# Shield_V4_Connector.net
KiCad netlist of a schematic drawn in EasyEDA
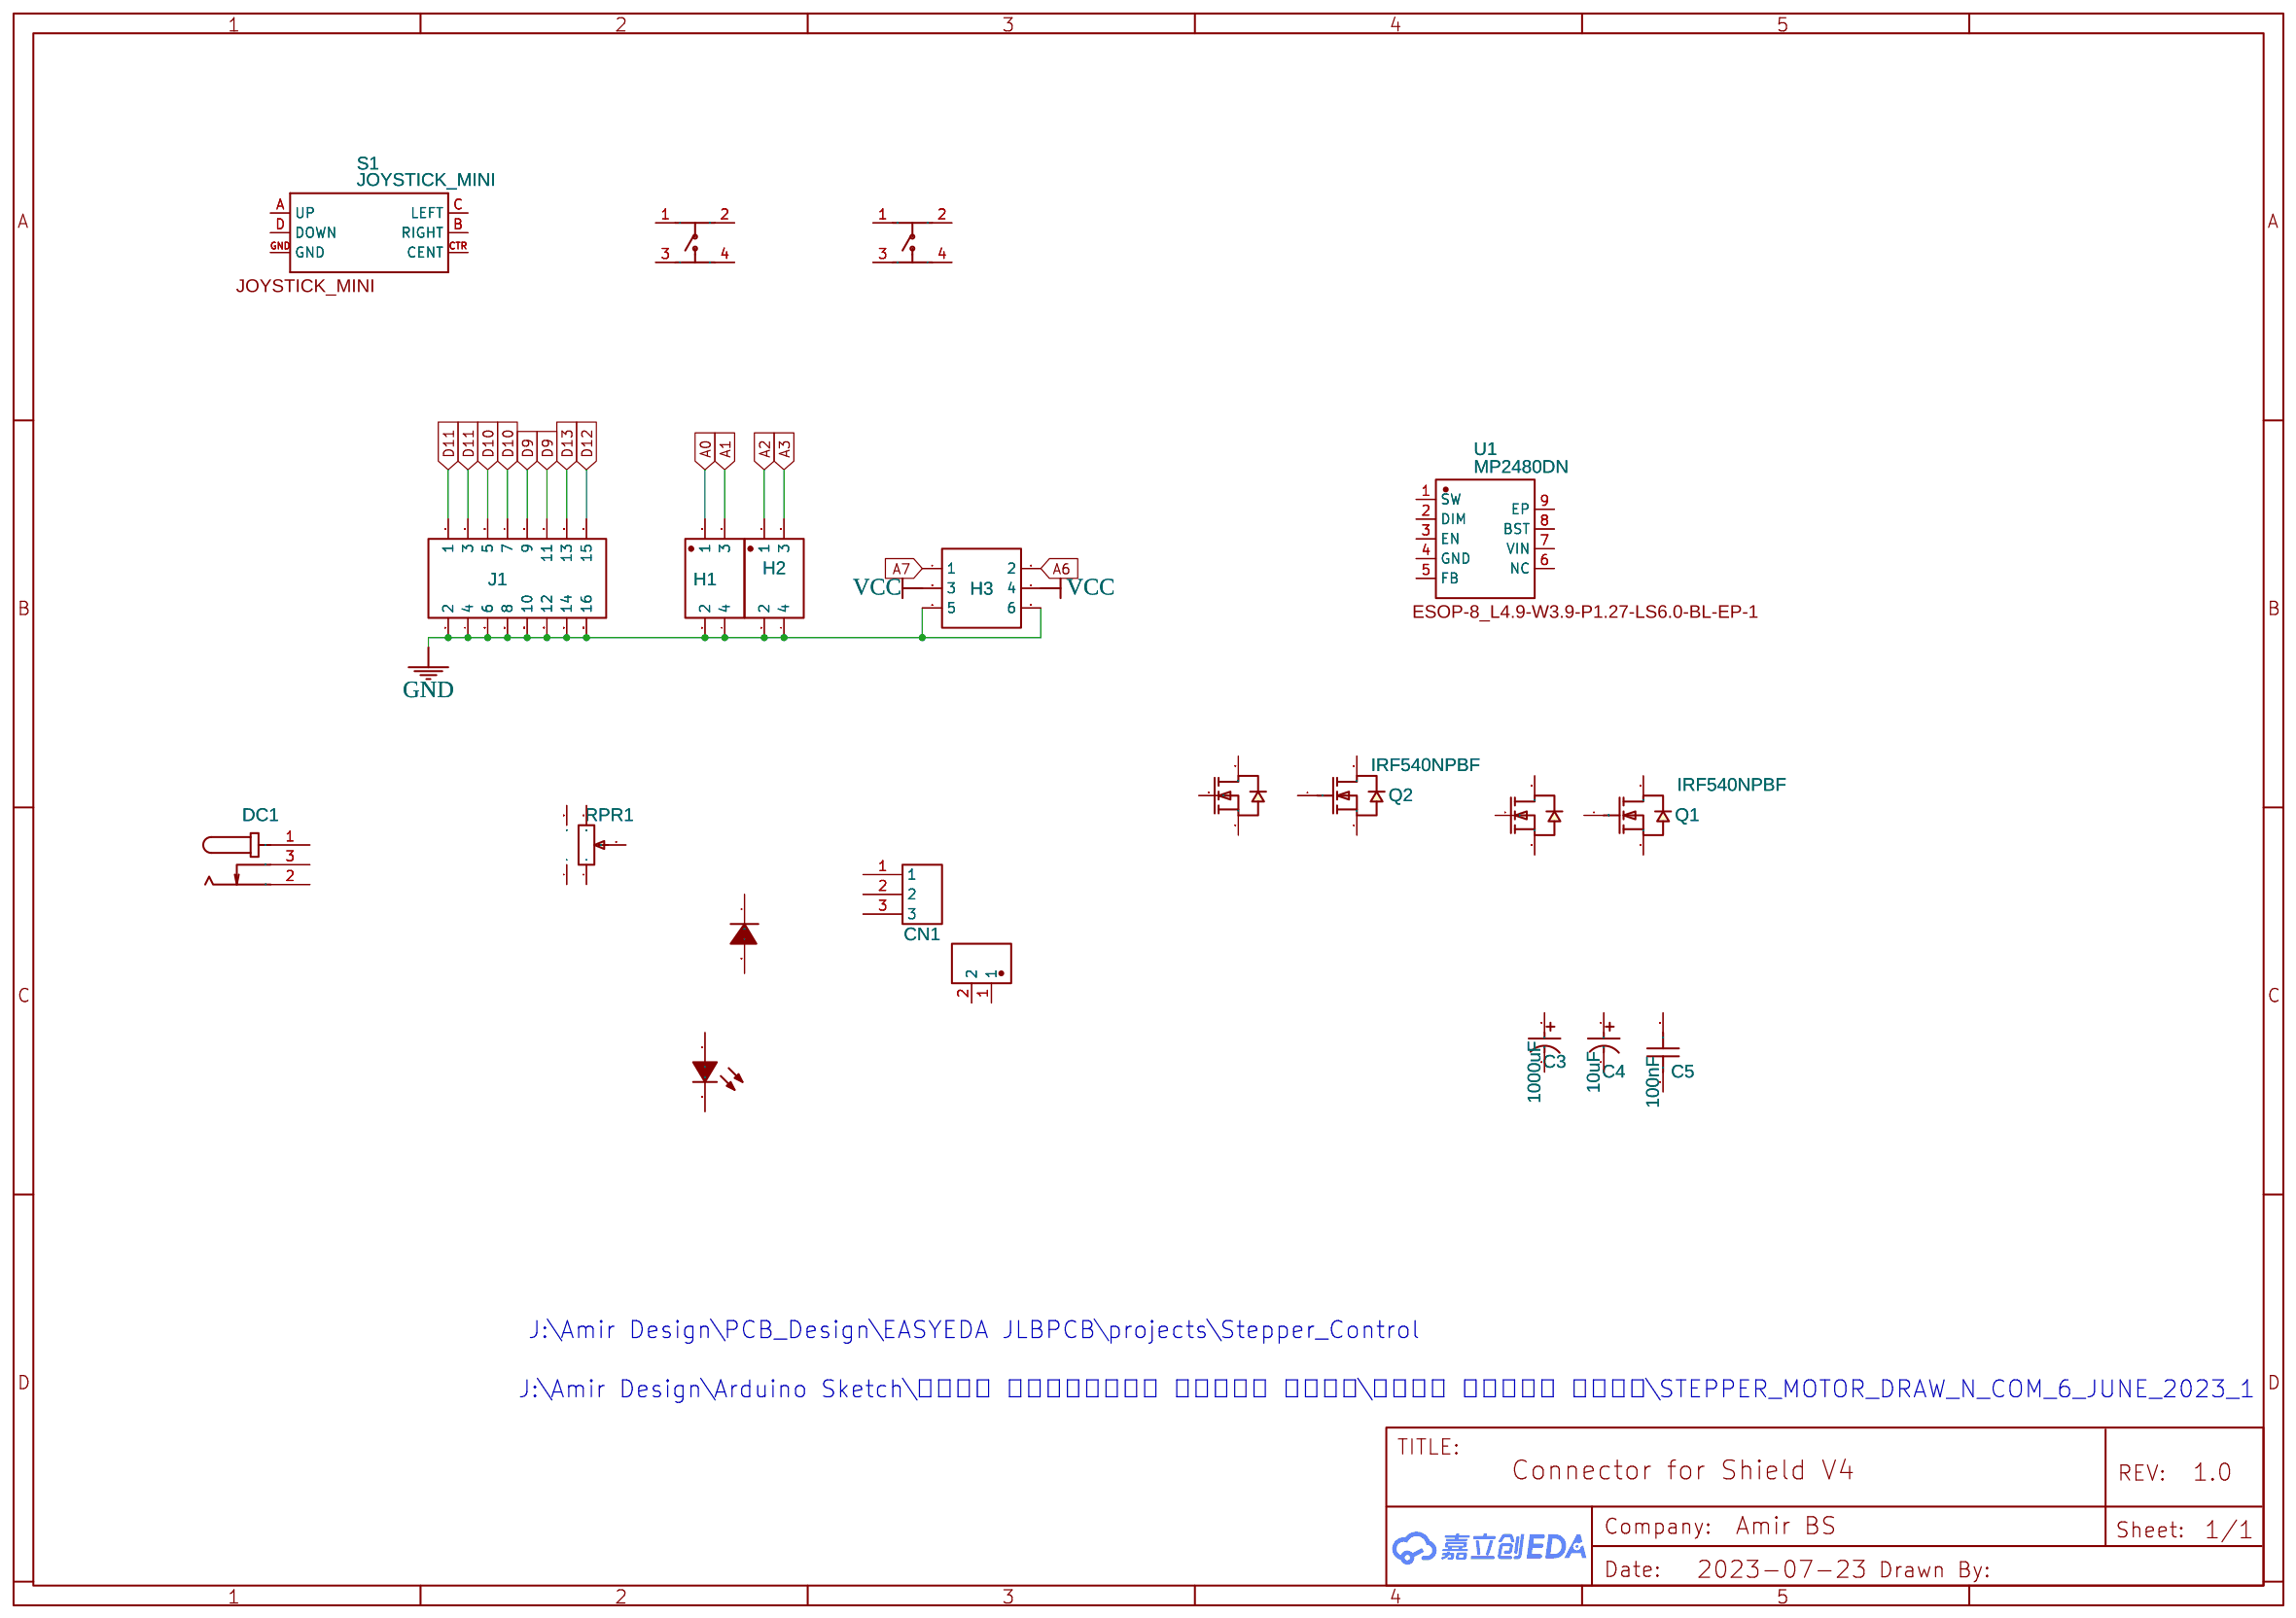
[diagram p0: schematic sheet]

(export (version "E")
  (design (tool "Eeschema 10.0.6"))
  (components
    (comp (ref "ACON1")
      (value "CON")
      (fields (field (name "BOM_Manufacturer Part") "PH-2AW") (field (name "BOM_Supplier Part") "C722769"))
      (libsource (lib "") (part "PH-2AW"))
    )
    (comp (ref "C3")
      (value "1000uF")
      (fields
        (field (name "BOM_Manufacturer Part") "KF102M025G200A")
        (field (name "BOM_Supplier Part") "C59326")
      )
      (libsource (lib "") (part "KF102M025G200A"))
    )
    (comp (ref "C4")
      (value "10uF")
      (fields
        (field (name "BOM_Manufacturer Part") "KF106M025C05RR0VH2FP0")
        (field (name "BOM_Supplier Part") "C43846")
      )
      (libsource (lib "") (part "10uF 25V 4*5"))
    )
    (comp (ref "C5")
      (value "100nF")
      (fields
        (field (name "BOM_Manufacturer Part") "CC0603KRX7R9BB104")
        (field (name "BOM_Supplier Part") "C14663")
      )
      (libsource (lib "") (part "CC0603KRX7R9BB104"))
    )
    (comp (ref "CN1")
      (value "XHB-3A")
      (fields (field (name "BOM_Supplier Part") "C68817"))
      (libsource (lib "") (part "XHB-3A"))
    )
    (comp (ref "DC1")
      (value "DC")
      (fields
        (field (name "BOM_Manufacturer Part") "DC005-2.0MM")
        (field (name "BOM_Supplier Part") "C111567")
      )
      (libsource (lib "") (part "DC005-2.0MM"))
    )
    (comp (ref "H1")
      (value "Header-Female-2.54_2x2")
      (fields
        (field (name "BOM_Manufacturer Part") "DS1023-2*2SF11")
        (field (name "BOM_Supplier Part") "C92273")
      )
      (libsource (lib "") (part "Header-Female-2.54_2x2"))
    )
    (comp (ref "H2")
      (value "Header-Female-2.54_2x2")
      (fields
        (field (name "BOM_Manufacturer Part") "DS1023-2*2SF11")
        (field (name "BOM_Supplier Part") "C92273")
      )
      (libsource (lib "") (part "Header-Female-2.54_2x2"))
    )
    (comp (ref "H3")
      (value "Header-Female-2.54_2x3")
      (fields
        (field (name "BOM_Manufacturer Part") "DS1023-2*3SF11")
        (field (name "BOM_Supplier Part") "C92272")
      )
      (libsource (lib "") (part "Header-Female-2.54_2x3"))
    )
    (comp (ref "HQ1")
      (value "Q")
      (fields (field (name "BOM_Manufacturer Part") "JSM2302") (field (name "BOM_Supplier Part") "C916403"))
      (libsource (lib "") (part "JSM2302"))
    )
    (comp (ref "HQ2")
      (value "Q")
      (fields (field (name "BOM_Manufacturer Part") "JSM2302") (field (name "BOM_Supplier Part") "C916403"))
      (libsource (lib "") (part "JSM2302"))
    )
    (comp (ref "ID1")
      (value "D")
      (fields (field (name "BOM_Manufacturer Part") "1N4007F") (field (name "BOM_Supplier Part") "C110856"))
      (libsource (lib "") (part "1N4007F"))
    )
    (comp (ref "ILED1")
      (value "LED")
      (fields
        (field (name "BOM_Manufacturer Part") "19-217/BHC-ZL1M2RY/3T")
        (field (name "BOM_Supplier Part") "C72041")
      )
      (libsource (lib "") (part "19-217/BHC-ZL1M2RY/3T"))
    )
    (comp (ref "J1")
      (value "Header-Female-2.54_2x8")
      (fields (field (name "BOM_Manufacturer Part") "2.54-2*8P母") (field (name "BOM_Supplier Part") "C30734"))
      (libsource (lib "") (part "Header-Female-2.54_2x8"))
    )
    (comp (ref "KEY1")
      (value "B3F-4050")
      (fields (field (name "BOM_Supplier Part") "C86707"))
      (libsource (lib "") (part "B3F-4050"))
    )
    (comp (ref "KEY2")
      (value "B3F-4050")
      (fields (field (name "BOM_Supplier Part") "C86707"))
      (libsource (lib "") (part "B3F-4050"))
    )
    (comp (ref "Q1")
      (value "IRF540NPBF")
      (fields (field (name "Manufacturer") "Infineon(英飞凌)"))
      (libsource (lib "") (part "IRF540NPBF"))
    )
    (comp (ref "Q2")
      (value "IRF540NPBF")
      (fields (field (name "Manufacturer") "Infineon(英飞凌)"))
      (libsource (lib "") (part "IRF540NPBF"))
    )
    (comp (ref "RPR1")
      (value "长柄旋转电位器")
      (fields (field (name "BOM_Supplier Part") "C2874842"))
      (libsource (lib "") (part "长柄旋转电位器"))
    )
    (comp (ref "S1") (value "JOYSTICK_MINI") (libsource (lib "") (part "JOYSTICK_MINI")))
    (comp (ref "U1") (value "MP2480DN") (libsource (lib "") (part "MP2480DN")))
  )
  (nets
    (net (code "1") (name "A0") (class "Default")
      (node (ref "H1") (pin "1") (pinfunction "1_1") (pintype "unspecified"))
    )
    (net (code "2") (name "A1") (class "Default")
      (node (ref "H1") (pin "3") (pinfunction "3_3") (pintype "unspecified"))
    )
    (net (code "3") (name "A2") (class "Default")
      (node (ref "H2") (pin "1") (pinfunction "1_1") (pintype "unspecified"))
    )
    (net (code "4") (name "A3") (class "Default")
      (node (ref "H2") (pin "3") (pinfunction "3_3") (pintype "unspecified"))
    )
    (net (code "5") (name "A6") (class "Default")
      (node (ref "H3") (pin "2") (pinfunction "2_2") (pintype "input"))
    )
    (net (code "6") (name "A7") (class "Default")
      (node (ref "H3") (pin "1") (pinfunction "1_1") (pintype "input"))
    )
    (net (code "7") (name "D9") (class "Default")
      (node (ref "J1") (pin "11") (pinfunction "11_11") (pintype "input"))
      (node (ref "J1") (pin "9") (pinfunction "9_9") (pintype "input"))
    )
    (net (code "8") (name "D10") (class "Default")
      (node (ref "J1") (pin "5") (pinfunction "5_5") (pintype "input"))
      (node (ref "J1") (pin "7") (pinfunction "7_7") (pintype "input"))
    )
    (net (code "9") (name "D11") (class "Default")
      (node (ref "J1") (pin "1") (pinfunction "1_1") (pintype "input"))
      (node (ref "J1") (pin "3") (pinfunction "3_3") (pintype "input"))
    )
    (net (code "10") (name "D12") (class "Default")
      (node (ref "J1") (pin "15") (pinfunction "15_15") (pintype "input"))
    )
    (net (code "11") (name "D13") (class "Default")
      (node (ref "J1") (pin "13") (pinfunction "13_13") (pintype "input"))
    )
    (net (code "12") (name "GND") (class "Default")
      (node (ref "H1") (pin "2") (pinfunction "2_2") (pintype "unspecified"))
      (node (ref "H1") (pin "4") (pinfunction "4_4") (pintype "unspecified"))
      (node (ref "H2") (pin "2") (pinfunction "2_2") (pintype "unspecified"))
      (node (ref "H2") (pin "4") (pinfunction "4_4") (pintype "unspecified"))
      (node (ref "H3") (pin "5") (pinfunction "5_5") (pintype "input"))
      (node (ref "H3") (pin "6") (pinfunction "6_6") (pintype "input"))
      (node (ref "J1") (pin "10") (pinfunction "10_10") (pintype "input"))
      (node (ref "J1") (pin "12") (pinfunction "12_12") (pintype "input"))
      (node (ref "J1") (pin "14") (pinfunction "14_14") (pintype "input"))
      (node (ref "J1") (pin "16") (pinfunction "16_16") (pintype "input"))
      (node (ref "J1") (pin "2") (pinfunction "2_2") (pintype "input"))
      (node (ref "J1") (pin "4") (pinfunction "4_4") (pintype "input"))
      (node (ref "J1") (pin "6") (pinfunction "6_6") (pintype "input"))
      (node (ref "J1") (pin "8") (pinfunction "8_8") (pintype "input"))
    )
    (net (code "13") (name "VCC") (class "Default")
      (node (ref "H3") (pin "3") (pinfunction "3_3") (pintype "input"))
      (node (ref "H3") (pin "4") (pinfunction "4_4") (pintype "input"))
    )
    (net (code "14") (name "unconnected-(ACON1-Pad1)") (class "Default")
      (node (ref "ACON1") (pin "1") (pinfunction "1_1") (pintype "unspecified"))
    )
    (net (code "15") (name "unconnected-(ACON1-Pad2)") (class "Default")
      (node (ref "ACON1") (pin "2") (pinfunction "2_2") (pintype "unspecified"))
    )
    (net (code "16") (name "unconnected-(C3-Pad1)") (class "Default")
      (node (ref "C3") (pin "1") (pinfunction "1_1") (pintype "input"))
    )
    (net (code "17") (name "unconnected-(C3-Pad2)") (class "Default")
      (node (ref "C3") (pin "2") (pinfunction "2_2") (pintype "input"))
    )
    (net (code "18") (name "unconnected-(C4-Pad1)") (class "Default")
      (node (ref "C4") (pin "1") (pinfunction "1_1") (pintype "input"))
    )
    (net (code "19") (name "unconnected-(C4-Pad2)") (class "Default")
      (node (ref "C4") (pin "2") (pinfunction "2_2") (pintype "input"))
    )
    (net (code "20") (name "unconnected-(C5-Pad1)") (class "Default")
      (node (ref "C5") (pin "1") (pinfunction "1_1") (pintype "unspecified"))
    )
    (net (code "21") (name "unconnected-(C5-Pad2)") (class "Default")
      (node (ref "C5") (pin "2") (pinfunction "2_2") (pintype "unspecified"))
    )
    (net (code "22") (name "unconnected-(CN1-Pad1)") (class "Default")
      (node (ref "CN1") (pin "1") (pinfunction "1_1") (pintype "unspecified"))
    )
    (net (code "23") (name "unconnected-(CN1-Pad2)") (class "Default")
      (node (ref "CN1") (pin "2") (pinfunction "2_2") (pintype "unspecified"))
    )
    (net (code "24") (name "unconnected-(CN1-Pad3)") (class "Default")
      (node (ref "CN1") (pin "3") (pinfunction "3_3") (pintype "unspecified"))
    )
    (net (code "25") (name "unconnected-(DC1-Pad1)") (class "Default")
      (node (ref "DC1") (pin "1") (pinfunction "1_1") (pintype "unspecified"))
    )
    (net (code "26") (name "unconnected-(DC1-Pad2)") (class "Default")
      (node (ref "DC1") (pin "2") (pinfunction "2_2") (pintype "unspecified"))
    )
    (net (code "27") (name "unconnected-(DC1-Pad3)") (class "Default")
      (node (ref "DC1") (pin "3") (pinfunction "3_3") (pintype "unspecified"))
    )
    (net (code "28") (name "unconnected-(HQ1-D-Pad3)") (class "Default")
      (node (ref "HQ1") (pin "3") (pinfunction "D_3") (pintype "unspecified"))
    )
    (net (code "29") (name "unconnected-(HQ1-G-Pad1)") (class "Default")
      (node (ref "HQ1") (pin "1") (pinfunction "G_1") (pintype "unspecified"))
    )
    (net (code "30") (name "unconnected-(HQ1-S-Pad2)") (class "Default")
      (node (ref "HQ1") (pin "2") (pinfunction "S_2") (pintype "unspecified"))
    )
    (net (code "31") (name "unconnected-(HQ2-D-Pad3)") (class "Default")
      (node (ref "HQ2") (pin "3") (pinfunction "D_3") (pintype "unspecified"))
    )
    (net (code "32") (name "unconnected-(HQ2-G-Pad1)") (class "Default")
      (node (ref "HQ2") (pin "1") (pinfunction "G_1") (pintype "unspecified"))
    )
    (net (code "33") (name "unconnected-(HQ2-S-Pad2)") (class "Default")
      (node (ref "HQ2") (pin "2") (pinfunction "S_2") (pintype "unspecified"))
    )
    (net (code "34") (name "unconnected-(ID1-A-Pad2)") (class "Default")
      (node (ref "ID1") (pin "2") (pinfunction "A_2") (pintype "unspecified"))
    )
    (net (code "35") (name "unconnected-(ID1-C-Pad1)") (class "Default")
      (node (ref "ID1") (pin "1") (pinfunction "C_1") (pintype "unspecified"))
    )
    (net (code "36") (name "unconnected-(ILED1-A-Pad1)") (class "Default")
      (node (ref "ILED1") (pin "1") (pinfunction "A_1") (pintype "input"))
    )
    (net (code "37") (name "unconnected-(ILED1-C-Pad2)") (class "Default")
      (node (ref "ILED1") (pin "2") (pinfunction "C_2") (pintype "input"))
    )
    (net (code "38") (name "unconnected-(KEY1-Pad1)") (class "Default")
      (node (ref "KEY1") (pin "1") (pinfunction "1_1") (pintype "unspecified"))
    )
    (net (code "39") (name "unconnected-(KEY1-Pad2)") (class "Default")
      (node (ref "KEY1") (pin "2") (pinfunction "2_2") (pintype "unspecified"))
    )
    (net (code "40") (name "unconnected-(KEY1-Pad3)") (class "Default")
      (node (ref "KEY1") (pin "3") (pinfunction "3_3") (pintype "unspecified"))
    )
    (net (code "41") (name "unconnected-(KEY1-Pad4)") (class "Default")
      (node (ref "KEY1") (pin "4") (pinfunction "4_4") (pintype "unspecified"))
    )
    (net (code "42") (name "unconnected-(KEY2-Pad1)") (class "Default")
      (node (ref "KEY2") (pin "1") (pinfunction "1_1") (pintype "unspecified"))
    )
    (net (code "43") (name "unconnected-(KEY2-Pad2)") (class "Default")
      (node (ref "KEY2") (pin "2") (pinfunction "2_2") (pintype "unspecified"))
    )
    (net (code "44") (name "unconnected-(KEY2-Pad3)") (class "Default")
      (node (ref "KEY2") (pin "3") (pinfunction "3_3") (pintype "unspecified"))
    )
    (net (code "45") (name "unconnected-(KEY2-Pad4)") (class "Default")
      (node (ref "KEY2") (pin "4") (pinfunction "4_4") (pintype "unspecified"))
    )
    (net (code "46") (name "unconnected-(Q1-D-Pad2)") (class "Default")
      (node (ref "Q1") (pin "2") (pinfunction "D_2") (pintype "unspecified"))
    )
    (net (code "47") (name "unconnected-(Q1-G-Pad1)") (class "Default")
      (node (ref "Q1") (pin "1") (pinfunction "G_1") (pintype "unspecified"))
    )
    (net (code "48") (name "unconnected-(Q1-S-Pad3)") (class "Default")
      (node (ref "Q1") (pin "3") (pinfunction "S_3") (pintype "unspecified"))
    )
    (net (code "49") (name "unconnected-(Q2-D-Pad2)") (class "Default")
      (node (ref "Q2") (pin "2") (pinfunction "D_2") (pintype "unspecified"))
    )
    (net (code "50") (name "unconnected-(Q2-G-Pad1)") (class "Default")
      (node (ref "Q2") (pin "1") (pinfunction "G_1") (pintype "unspecified"))
    )
    (net (code "51") (name "unconnected-(Q2-S-Pad3)") (class "Default")
      (node (ref "Q2") (pin "3") (pinfunction "S_3") (pintype "unspecified"))
    )
    (net (code "52") (name "unconnected-(RPR1-Pad1)") (class "Default")
      (node (ref "RPR1") (pin "1") (pinfunction "1_1") (pintype "input"))
    )
    (net (code "53") (name "unconnected-(RPR1-Pad2)") (class "Default")
      (node (ref "RPR1") (pin "2") (pinfunction "2_2") (pintype "input"))
    )
    (net (code "54") (name "unconnected-(RPR1-Pad3)") (class "Default")
      (node (ref "RPR1") (pin "3") (pinfunction "3_3") (pintype "input"))
    )
    (net (code "55") (name "unconnected-(RPR1-Pad4)") (class "Default")
      (node (ref "RPR1") (pin "4") (pinfunction "4_4") (pintype "input"))
    )
    (net (code "56") (name "unconnected-(RPR1-Pad5)") (class "Default")
      (node (ref "RPR1") (pin "5") (pinfunction "5_5") (pintype "input"))
    )
    (net (code "57") (name "unconnected-(S1-CENT-PadCTR)") (class "Default")
      (node (ref "S1") (pin "CTR") (pinfunction "CENT_CTR") (pintype "unspecified"))
    )
    (net (code "58") (name "unconnected-(S1-DOWN-PadD)") (class "Default")
      (node (ref "S1") (pin "D") (pinfunction "DOWN_D") (pintype "unspecified"))
    )
    (net (code "59") (name "unconnected-(S1-LEFT-PadC)") (class "Default")
      (node (ref "S1") (pin "C") (pinfunction "LEFT_C") (pintype "unspecified"))
    )
    (net (code "60") (name "unconnected-(S1-PadGND)") (class "Default")
      (node (ref "S1") (pin "GND") (pinfunction "GND_GND") (pintype "unspecified"))
    )
    (net (code "61") (name "unconnected-(S1-RIGHT-PadB)") (class "Default")
      (node (ref "S1") (pin "B") (pinfunction "RIGHT_B") (pintype "unspecified"))
    )
    (net (code "62") (name "unconnected-(S1-UP-PadA)") (class "Default")
      (node (ref "S1") (pin "A") (pinfunction "UP_A") (pintype "unspecified"))
    )
    (net (code "63") (name "unconnected-(U1-BST-Pad8)") (class "Default")
      (node (ref "U1") (pin "8") (pinfunction "BST_8") (pintype "unspecified"))
    )
    (net (code "64") (name "unconnected-(U1-DIM-Pad2)") (class "Default")
      (node (ref "U1") (pin "2") (pinfunction "DIM_2") (pintype "unspecified"))
    )
    (net (code "65") (name "unconnected-(U1-EN-Pad3)") (class "Default")
      (node (ref "U1") (pin "3") (pinfunction "EN_3") (pintype "unspecified"))
    )
    (net (code "66") (name "unconnected-(U1-EP-Pad9)") (class "Default")
      (node (ref "U1") (pin "9") (pinfunction "EP_9") (pintype "unspecified"))
    )
    (net (code "67") (name "unconnected-(U1-FB-Pad5)") (class "Default")
      (node (ref "U1") (pin "5") (pinfunction "FB_5") (pintype "unspecified"))
    )
    (net (code "68") (name "unconnected-(U1-GND-Pad4)") (class "Default")
      (node (ref "U1") (pin "4") (pinfunction "GND_4") (pintype "unspecified"))
    )
    (net (code "69") (name "unconnected-(U1-NC-Pad6)") (class "Default")
      (node (ref "U1") (pin "6") (pinfunction "NC_6") (pintype "unspecified"))
    )
    (net (code "70") (name "unconnected-(U1-SW-Pad1)") (class "Default")
      (node (ref "U1") (pin "1") (pinfunction "SW_1") (pintype "unspecified"))
    )
    (net (code "71") (name "unconnected-(U1-VIN-Pad7)") (class "Default")
      (node (ref "U1") (pin "7") (pinfunction "VIN_7") (pintype "unspecified"))
    )
  )
)
